# bengkel_elektronika_penghitung_otomatis.net
KiCad netlist of a schematic drawn in EAGLE
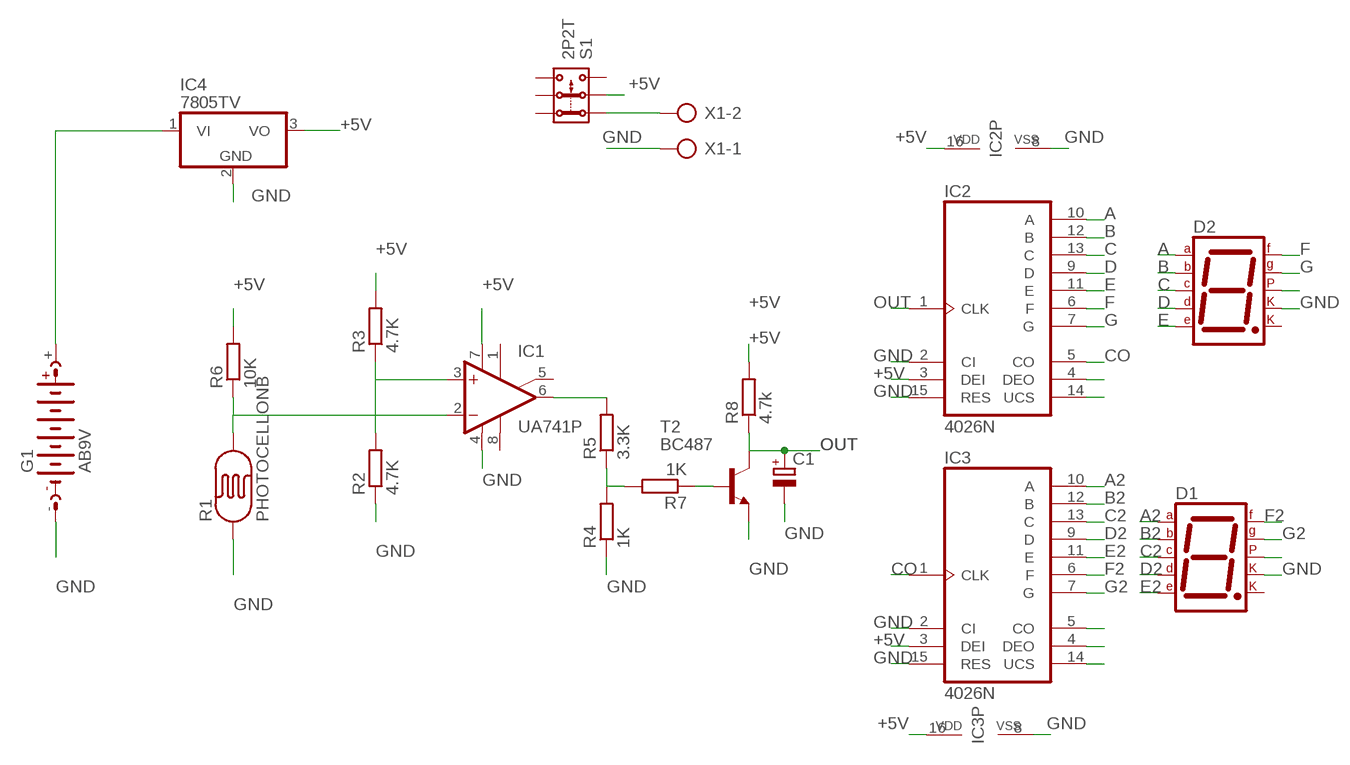
[diagram p0: schematic, sheet 1]

(export (version "E")
  (design (tool "Eeschema 10.0.6"))
  (components
    (comp (ref "C1")
      (value "CPOL-EUE2-4")
      (footprint "eagle-import:E2-4")
      (libsource (lib "eagle-import") (part "CPOL-EUE2-4"))
    )
    (comp (ref "D1")
      (value "7SEG-CK")
      (footprint "eagle-import:7SEG-13")
      (libsource (lib "eagle-import") (part "7SEG-CK"))
    )
    (comp (ref "D2")
      (value "7SEG-CK")
      (footprint "eagle-import:7SEG-13")
      (libsource (lib "eagle-import") (part "7SEG-CK"))
    )
    (comp (ref "G1")
      (value "AB9V")
      (footprint "eagle-import:AB9V")
      (libsource (lib "eagle-import") (part "AB9V"))
    )
    (comp (ref "IC1")
      (value "UA741P")
      (footprint "eagle-import:DIL08")
      (libsource (lib "eagle-import") (part "741PUA"))
    )
    (comp (ref "IC2")
      (value "4026N")
      (footprint "eagle-import:DIL16")
      (libsource (lib "eagle-import") (part "4026N"))
    )
    (comp (ref "IC3")
      (value "4026N")
      (footprint "eagle-import:DIL16")
      (libsource (lib "eagle-import") (part "4026N"))
    )
    (comp (ref "IC4")
      (value "7805TV")
      (footprint "eagle-import:TO220V")
      (libsource (lib "eagle-import") (part "78TV05"))
    )
    (comp (ref "R1")
      (value "PHOTOCELLONB")
      (footprint "eagle-import:ON_BOARD")
      (libsource (lib "eagle-import") (part "PHOTOCELLONB"))
    )
    (comp (ref "R2")
      (value "4.7K")
      (footprint "eagle-import:0207_7")
      (libsource (lib "eagle-import") (part "R-EU_0207/7"))
    )
    (comp (ref "R3")
      (value "4.7K")
      (footprint "eagle-import:0207_7")
      (libsource (lib "eagle-import") (part "R-EU_0207/7"))
    )
    (comp (ref "R4")
      (value "1K")
      (footprint "eagle-import:0207_7")
      (libsource (lib "eagle-import") (part "R-EU_0207/7"))
    )
    (comp (ref "R5")
      (value "3.3K")
      (footprint "eagle-import:0207_7")
      (libsource (lib "eagle-import") (part "R-EU_0207/7"))
    )
    (comp (ref "R6")
      (value "10K")
      (footprint "eagle-import:0207_7")
      (libsource (lib "eagle-import") (part "R-EU_0207/7"))
    )
    (comp (ref "R7")
      (value "1K")
      (footprint "eagle-import:0207_7")
      (libsource (lib "eagle-import") (part "R-EU_0207/7"))
    )
    (comp (ref "R8")
      (value "4.7k")
      (footprint "eagle-import:0207_7")
      (libsource (lib "eagle-import") (part "R-EU_0207/7"))
    )
    (comp (ref "S1")
      (value "2P2T")
      (footprint "eagle-import:2P2T")
      (libsource (lib "eagle-import") (part "2P2T"))
    )
    (comp (ref "T2")
      (value "BC487")
      (footprint "eagle-import:TO92-EBC")
      (libsource (lib "eagle-import") (part "BC487"))
    )
    (comp (ref "X1")
      (value "AK500/2")
      (footprint "eagle-import:AK500_2")
      (libsource (lib "eagle-import") (part "AK500/2"))
    )
  )
  (nets
    (net (code "1") (name "/+5V") (class "Default")
      (node (ref "IC1") (pin "7") (pinfunction "V+_7") (pintype "power_in"))
      (node (ref "IC2") (pin "16") (pinfunction "VDD_16") (pintype "power_in"))
      (node (ref "IC2") (pin "3") (pinfunction "DEI_3") (pintype "input"))
      (node (ref "IC3") (pin "16") (pinfunction "VDD_16") (pintype "power_in"))
      (node (ref "IC3") (pin "3") (pinfunction "DEI_3") (pintype "input"))
      (node (ref "IC4") (pin "3") (pinfunction "VO_3") (pintype "passive"))
      (node (ref "R3") (pin "2") (pinfunction "2_2") (pintype "passive"))
      (node (ref "R6") (pin "2") (pinfunction "2_2") (pintype "passive"))
      (node (ref "R8") (pin "2") (pinfunction "2_2") (pintype "passive"))
      (node (ref "S1") (pin "2.1") (pinfunction "2.1_2.1") (pintype "passive"))
    )
    (net (code "2") (name "/A") (class "Default")
      (node (ref "D2") (pin "7") (pinfunction "A_7") (pintype "passive"))
      (node (ref "IC2") (pin "10") (pinfunction "A_10") (pintype "output"))
    )
    (net (code "3") (name "/A2") (class "Default")
      (node (ref "D1") (pin "7") (pinfunction "A_7") (pintype "passive"))
      (node (ref "IC3") (pin "10") (pinfunction "A_10") (pintype "output"))
    )
    (net (code "4") (name "/B") (class "Default")
      (node (ref "D2") (pin "6") (pinfunction "B_6") (pintype "passive"))
      (node (ref "IC2") (pin "12") (pinfunction "B_12") (pintype "output"))
    )
    (net (code "5") (name "/B2") (class "Default")
      (node (ref "D1") (pin "6") (pinfunction "B_6") (pintype "passive"))
      (node (ref "IC3") (pin "12") (pinfunction "B_12") (pintype "output"))
    )
    (net (code "6") (name "/C") (class "Default")
      (node (ref "D2") (pin "4") (pinfunction "C_4") (pintype "passive"))
      (node (ref "IC2") (pin "13") (pinfunction "C_13") (pintype "output"))
    )
    (net (code "7") (name "/C2") (class "Default")
      (node (ref "D1") (pin "4") (pinfunction "C_4") (pintype "passive"))
      (node (ref "IC3") (pin "13") (pinfunction "C_13") (pintype "output"))
    )
    (net (code "8") (name "/CO") (class "Default")
      (node (ref "IC2") (pin "5") (pinfunction "CO_5") (pintype "output"))
      (node (ref "IC3") (pin "1") (pinfunction "CLK_1") (pintype "input"))
    )
    (net (code "9") (name "/D") (class "Default")
      (node (ref "D2") (pin "2") (pinfunction "D_2") (pintype "passive"))
      (node (ref "IC2") (pin "9") (pinfunction "D_9") (pintype "output"))
    )
    (net (code "10") (name "/D2") (class "Default")
      (node (ref "D1") (pin "2") (pinfunction "D_2") (pintype "passive"))
      (node (ref "IC3") (pin "9") (pinfunction "D_9") (pintype "output"))
    )
    (net (code "11") (name "/E") (class "Default")
      (node (ref "D2") (pin "1") (pinfunction "E_1") (pintype "passive"))
      (node (ref "IC2") (pin "11") (pinfunction "E_11") (pintype "output"))
    )
    (net (code "12") (name "/E2") (class "Default")
      (node (ref "D1") (pin "1") (pinfunction "E_1") (pintype "passive"))
      (node (ref "IC3") (pin "11") (pinfunction "E_11") (pintype "output"))
    )
    (net (code "13") (name "/F") (class "Default")
      (node (ref "D2") (pin "9") (pinfunction "F_9") (pintype "passive"))
      (node (ref "IC2") (pin "6") (pinfunction "F_6") (pintype "output"))
    )
    (net (code "14") (name "/F2") (class "Default")
      (node (ref "D1") (pin "9") (pinfunction "F_9") (pintype "passive"))
      (node (ref "IC3") (pin "6") (pinfunction "F_6") (pintype "output"))
    )
    (net (code "15") (name "/G") (class "Default")
      (node (ref "D2") (pin "10") (pinfunction "G_10") (pintype "passive"))
      (node (ref "IC2") (pin "7") (pinfunction "G_7") (pintype "output"))
    )
    (net (code "16") (name "/G2") (class "Default")
      (node (ref "D1") (pin "10") (pinfunction "G_10") (pintype "passive"))
      (node (ref "IC3") (pin "7") (pinfunction "G_7") (pintype "output"))
    )
    (net (code "17") (name "/GND") (class "Default")
      (node (ref "C1") (pin "-") (pinfunction "-_-") (pintype "passive"))
      (node (ref "D1") (pin "3") (pinfunction "CK1_3") (pintype "passive"))
      (node (ref "D2") (pin "3") (pinfunction "CK1_3") (pintype "passive"))
      (node (ref "G1") (pin "-") (pinfunction "-_-") (pintype "passive"))
      (node (ref "IC1") (pin "4") (pinfunction "V-_4") (pintype "power_in"))
      (node (ref "IC2") (pin "15") (pinfunction "RES_15") (pintype "input"))
      (node (ref "IC2") (pin "2") (pinfunction "CI_2") (pintype "input"))
      (node (ref "IC2") (pin "8") (pinfunction "VSS_8") (pintype "power_in"))
      (node (ref "IC3") (pin "15") (pinfunction "RES_15") (pintype "input"))
      (node (ref "IC3") (pin "2") (pinfunction "CI_2") (pintype "input"))
      (node (ref "IC3") (pin "8") (pinfunction "VSS_8") (pintype "power_in"))
      (node (ref "IC4") (pin "2") (pinfunction "GND_2") (pintype "passive"))
      (node (ref "R1") (pin "1") (pinfunction "P$1_1") (pintype "bidirectional"))
      (node (ref "R2") (pin "1") (pinfunction "1_1") (pintype "passive"))
      (node (ref "R4") (pin "1") (pinfunction "1_1") (pintype "passive"))
      (node (ref "T2") (pin "E") (pinfunction "E_E") (pintype "passive"))
      (node (ref "X1") (pin "1") (pinfunction "KL_1") (pintype "passive"))
    )
    (net (code "18") (name "/OUT") (class "Default")
      (node (ref "C1") (pin "+") (pinfunction "+_+") (pintype "passive"))
      (node (ref "IC2") (pin "1") (pinfunction "CLK_1") (pintype "input"))
      (node (ref "R8") (pin "1") (pinfunction "1_1") (pintype "passive"))
      (node (ref "T2") (pin "C") (pinfunction "C_C") (pintype "passive"))
    )
    (net (code "19") (name "Net-(IC1-+IN)") (class "Default")
      (node (ref "IC1") (pin "3") (pinfunction "+IN_3") (pintype "input"))
      (node (ref "R2") (pin "2") (pinfunction "2_2") (pintype "passive"))
      (node (ref "R3") (pin "1") (pinfunction "1_1") (pintype "passive"))
    )
    (net (code "20") (name "Net-(IC1--IN)") (class "Default")
      (node (ref "IC1") (pin "2") (pinfunction "-IN_2") (pintype "input"))
      (node (ref "R1") (pin "2") (pinfunction "P$2_2") (pintype "bidirectional"))
      (node (ref "R6") (pin "1") (pinfunction "1_1") (pintype "passive"))
    )
    (net (code "21") (name "Net-(IC1-OUT)") (class "Default")
      (node (ref "IC1") (pin "6") (pinfunction "OUT_6") (pintype "output"))
      (node (ref "R5") (pin "2") (pinfunction "2_2") (pintype "passive"))
    )
    (net (code "22") (name "Net-(IC4-VI)") (class "Default")
      (node (ref "G1") (pin "+") (pinfunction "+_+") (pintype "passive"))
      (node (ref "IC4") (pin "1") (pinfunction "VI_1") (pintype "input"))
    )
    (net (code "23") (name "Net-(R4-Pad2)") (class "Default")
      (node (ref "R4") (pin "2") (pinfunction "2_2") (pintype "passive"))
      (node (ref "R5") (pin "1") (pinfunction "1_1") (pintype "passive"))
      (node (ref "R7") (pin "2") (pinfunction "2_2") (pintype "passive"))
    )
    (net (code "24") (name "Net-(R7-Pad1)") (class "Default")
      (node (ref "R7") (pin "1") (pinfunction "1_1") (pintype "passive"))
      (node (ref "T2") (pin "B") (pinfunction "B_B") (pintype "passive"))
    )
    (net (code "25") (name "Net-(X1B-KL)") (class "Default")
      (node (ref "S1") (pin "1.1") (pinfunction "1.1_1.1") (pintype "passive"))
      (node (ref "X1") (pin "2") (pinfunction "KL_2") (pintype "passive"))
    )
    (net (code "26") (name "unconnected-(D1-CK2-Pad8)") (class "Default")
      (node (ref "D1") (pin "8") (pinfunction "CK2_8") (pintype "passive"))
    )
    (net (code "27") (name "unconnected-(D1-DP-Pad5)") (class "Default")
      (node (ref "D1") (pin "5") (pinfunction "DP_5") (pintype "passive"))
    )
    (net (code "28") (name "unconnected-(D2-CK2-Pad8)") (class "Default")
      (node (ref "D2") (pin "8") (pinfunction "CK2_8") (pintype "passive"))
    )
    (net (code "29") (name "unconnected-(D2-DP-Pad5)") (class "Default")
      (node (ref "D2") (pin "5") (pinfunction "DP_5") (pintype "passive"))
    )
    (net (code "30") (name "unconnected-(IC1-ON1-Pad1)") (class "Default")
      (node (ref "IC1") (pin "1") (pinfunction "ON1_1") (pintype "passive"))
    )
    (net (code "31") (name "unconnected-(IC1-ON2-Pad5)") (class "Default")
      (node (ref "IC1") (pin "5") (pinfunction "ON2_5") (pintype "passive"))
    )
    (net (code "32") (name "unconnected-(IC1-OPT-Pad8)") (class "Default")
      (node (ref "IC1") (pin "8") (pinfunction "OPT_8") (pintype "passive"))
    )
    (net (code "33") (name "unconnected-(IC2A-DEO-Pad4)") (class "Default")
      (node (ref "IC2") (pin "4") (pinfunction "DEO_4") (pintype "output"))
    )
    (net (code "34") (name "unconnected-(IC2A-UCS-Pad14)") (class "Default")
      (node (ref "IC2") (pin "14") (pinfunction "UCS_14") (pintype "output"))
    )
    (net (code "35") (name "unconnected-(IC3A-CO-Pad5)") (class "Default")
      (node (ref "IC3") (pin "5") (pinfunction "CO_5") (pintype "output"))
    )
    (net (code "36") (name "unconnected-(IC3A-DEO-Pad4)") (class "Default")
      (node (ref "IC3") (pin "4") (pinfunction "DEO_4") (pintype "output"))
    )
    (net (code "37") (name "unconnected-(IC3A-UCS-Pad14)") (class "Default")
      (node (ref "IC3") (pin "14") (pinfunction "UCS_14") (pintype "output"))
    )
    (net (code "38") (name "unconnected-(S1-Pad1.2)") (class "Default")
      (node (ref "S1") (pin "1.2") (pinfunction "1.2_1.2") (pintype "passive"))
    )
    (net (code "39") (name "unconnected-(S1-Pad2.2)") (class "Default")
      (node (ref "S1") (pin "2.2") (pinfunction "2.2_2.2") (pintype "passive"))
    )
    (net (code "40") (name "unconnected-(S1-Pad3.1)") (class "Default")
      (node (ref "S1") (pin "3.1") (pinfunction "3.1_3.1") (pintype "passive"))
    )
    (net (code "41") (name "unconnected-(S1-Pad3.2)") (class "Default")
      (node (ref "S1") (pin "3.2") (pinfunction "3.2_3.2") (pintype "passive"))
    )
  )
)
